# mixer.net
KiCad netlist of a schematic drawn in EAGLE
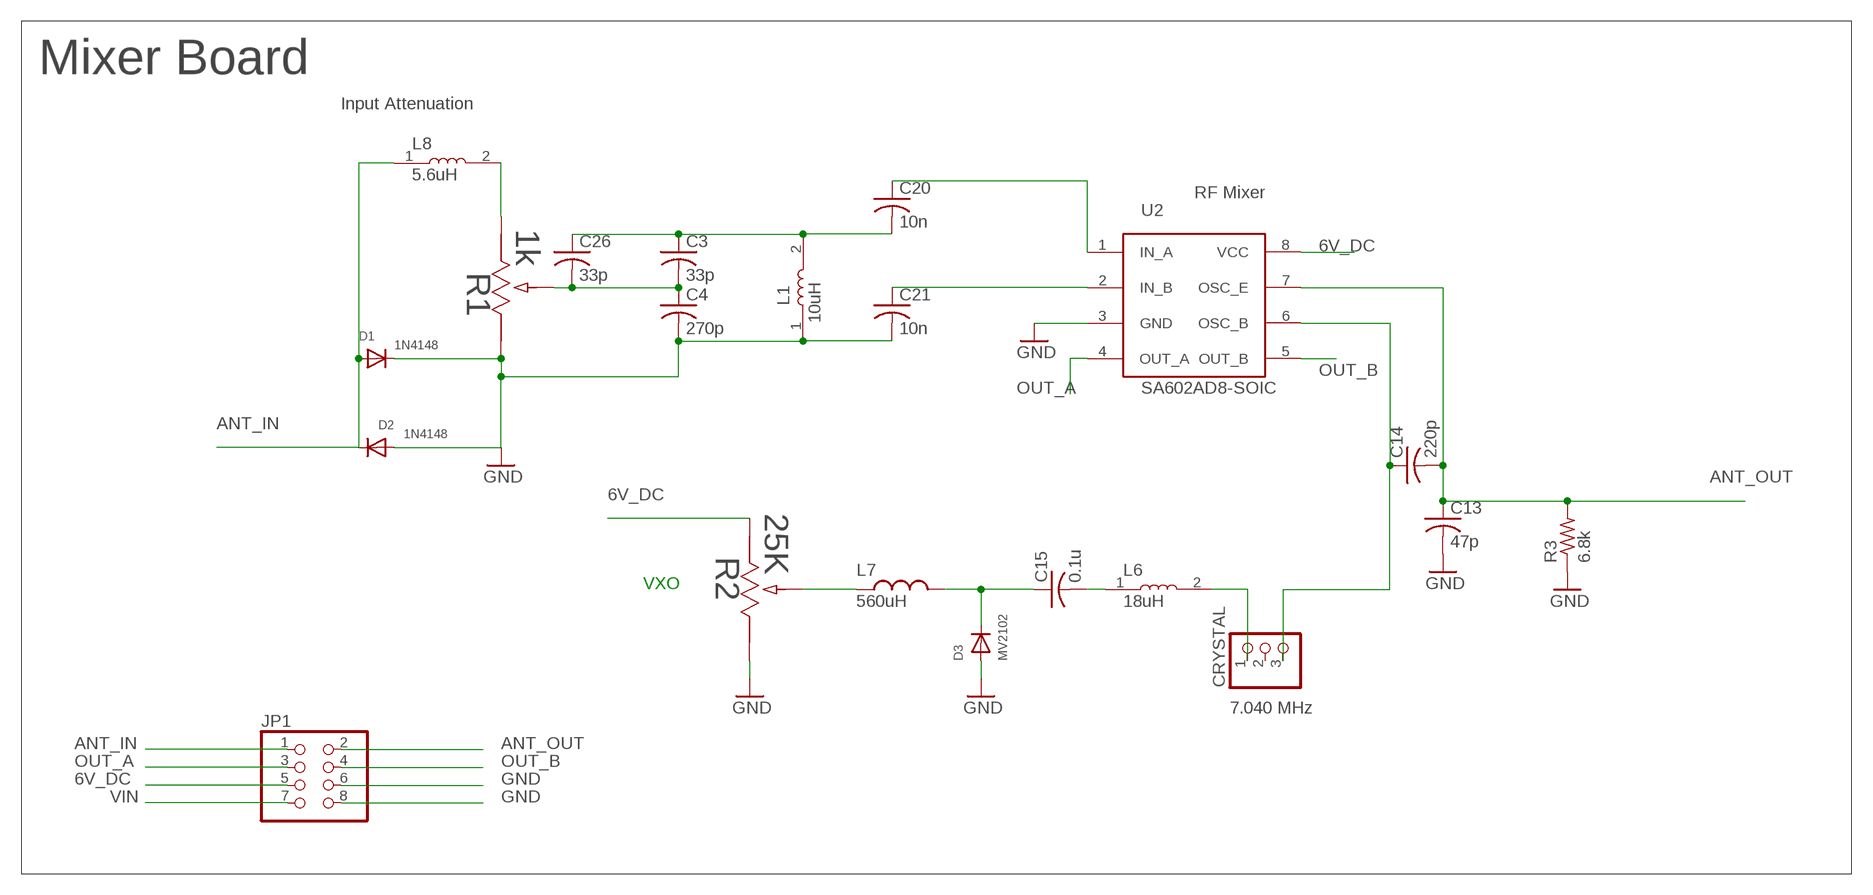
[diagram p0: schematic, sheet 1]

(export (version "E")
  (design (tool "Eeschema 10.0.6"))
  (components
    (comp (ref "C3")
      (value "33p")
      (footprint "eagle-import:C0805")
      (libsource (lib "eagle-import") (part "C-USC0805"))
    )
    (comp (ref "C4")
      (value "270p")
      (footprint "eagle-import:C0805")
      (libsource (lib "eagle-import") (part "C-USC0805"))
    )
    (comp (ref "C13")
      (value "47p")
      (footprint "eagle-import:C0805")
      (libsource (lib "eagle-import") (part "C-USC0805"))
    )
    (comp (ref "C14")
      (value "220p")
      (footprint "eagle-import:C0805")
      (libsource (lib "eagle-import") (part "C-USC0805"))
    )
    (comp (ref "C15")
      (value "0.1u")
      (footprint "eagle-import:C0805")
      (libsource (lib "eagle-import") (part "C-USC0805"))
    )
    (comp (ref "C20")
      (value "10n")
      (footprint "eagle-import:C0805")
      (libsource (lib "eagle-import") (part "C-USC0805"))
    )
    (comp (ref "C21")
      (value "10n")
      (footprint "eagle-import:C0805")
      (libsource (lib "eagle-import") (part "C-USC0805"))
    )
    (comp (ref "C26")
      (value "33p")
      (footprint "eagle-import:C0805")
      (libsource (lib "eagle-import") (part "C-USC0805"))
    )
    (comp (ref "CRYSTAL")
      (value "PINHD-1X3")
      (footprint "eagle-import:1X03")
      (libsource (lib "eagle-import") (part "PINHD-1X3"))
    )
    (comp (ref "D1")
      (value "1N4148")
      (footprint "eagle-import:SOD-123FL")
      (libsource (lib "eagle-import") (part "DIODE_SOD-123FL"))
    )
    (comp (ref "D2")
      (value "1N4148")
      (footprint "eagle-import:SOD-123FL")
      (libsource (lib "eagle-import") (part "DIODE_SOD-123FL"))
    )
    (comp (ref "D3")
      (value "MV2102")
      (footprint "eagle-import:SOD-323F")
      (libsource (lib "eagle-import") (part "DIODESOD-323F"))
    )
    (comp (ref "JP1")
      (value "PINHD-2X4")
      (footprint "eagle-import:2X04")
      (libsource (lib "eagle-import") (part "PINHD-2X4"))
    )
    (comp (ref "L1")
      (value "10uH")
      (footprint "eagle-import:INDC2012X87N")
      (fields (field (name "MF") "TDK") (field (name "MP") "MLF2012E5R6KT000"))
      (libsource (lib "eagle-import") (part "MLF2012E5R6KT000"))
    )
    (comp (ref "L6")
      (value "18uH")
      (footprint "eagle-import:INDC2012X87N")
      (fields (field (name "MF") "TDK") (field (name "MP") "MLF2012E5R6KT000"))
      (libsource (lib "eagle-import") (part "MLF2012E5R6KT000"))
    )
    (comp (ref "L7")
      (value "560uH")
      (footprint "eagle-import:INDM4532X340")
      (libsource (lib "eagle-import") (part "zort2_LMOLDED-1812(4532-METRIC)"))
    )
    (comp (ref "L8")
      (value "5.6uH")
      (footprint "eagle-import:INDC2012X87N")
      (fields (field (name "MF") "TDK") (field (name "MP") "MLF2012E5R6KT000"))
      (libsource (lib "eagle-import") (part "MLF2012E5R6KT000"))
    )
    (comp (ref "R1")
      (value "1k")
      (footprint "eagle-import:POT_3362W")
      (fields (field (name "MANUFACTURER_PART_NUMBER") "3362W-1-102LF"))
      (libsource (lib "eagle-import") (part "3362W-1-102LF"))
    )
    (comp (ref "R2")
      (value "25K")
      (footprint "eagle-import:POT_3362W")
      (fields (field (name "MANUFACTURER_PART_NUMBER") "3362W-1-102LF"))
      (libsource (lib "eagle-import") (part "3362W-1-102LF"))
    )
    (comp (ref "R3")
      (value "6.8k")
      (footprint "eagle-import:M0805")
      (libsource (lib "eagle-import") (part "R-US_M0805"))
    )
    (comp (ref "U2")
      (value "SA602AD8-SOIC")
      (footprint "eagle-import:SOIC127P599X175-8N")
      (libsource (lib "eagle-import") (part "SA602AD8-SOIC"))
    )
  )
  (nets
    (net (code "1") (name "/6V_DC") (class "Default")
      (node (ref "JP1") (pin "5") (pinfunction "5_5") (pintype "passive"))
      (node (ref "R2") (pin "1") (pinfunction "1_1") (pintype "passive"))
      (node (ref "U2") (pin "8") (pinfunction "VCC_8") (pintype "bidirectional"))
    )
    (net (code "2") (name "/ANT_IN") (class "Default")
      (node (ref "D1") (pin "A") (pinfunction "A_A") (pintype "passive"))
      (node (ref "D2") (pin "C") (pinfunction "C_C") (pintype "passive"))
      (node (ref "JP1") (pin "1") (pinfunction "1_1") (pintype "passive"))
      (node (ref "L8") (pin "1") (pinfunction "1_1") (pintype "passive"))
    )
    (net (code "3") (name "/ANT_OUT") (class "Default")
      (node (ref "C13") (pin "1") (pinfunction "1_1") (pintype "passive"))
      (node (ref "C14") (pin "2") (pinfunction "2_2") (pintype "passive"))
      (node (ref "JP1") (pin "2") (pinfunction "2_2") (pintype "passive"))
      (node (ref "R3") (pin "2") (pinfunction "2_2") (pintype "passive"))
      (node (ref "U2") (pin "7") (pinfunction "OSC_E_7") (pintype "bidirectional"))
    )
    (net (code "4") (name "/OUT_A") (class "Default")
      (node (ref "JP1") (pin "3") (pinfunction "3_3") (pintype "passive"))
      (node (ref "U2") (pin "4") (pinfunction "OUT_A_4") (pintype "bidirectional"))
    )
    (net (code "5") (name "/OUT_B") (class "Default")
      (node (ref "JP1") (pin "4") (pinfunction "4_4") (pintype "passive"))
      (node (ref "U2") (pin "5") (pinfunction "OUT_B_5") (pintype "bidirectional"))
    )
    (net (code "6") (name "/VIN") (class "Default")
      (node (ref "JP1") (pin "7") (pinfunction "7_7") (pintype "passive"))
    )
    (net (code "7") (name "GND") (class "Default")
      (node (ref "C13") (pin "2") (pinfunction "2_2") (pintype "passive"))
      (node (ref "C21") (pin "2") (pinfunction "2_2") (pintype "passive"))
      (node (ref "C4") (pin "2") (pinfunction "2_2") (pintype "passive"))
      (node (ref "D1") (pin "C") (pinfunction "C_C") (pintype "passive"))
      (node (ref "D2") (pin "A") (pinfunction "A_A") (pintype "passive"))
      (node (ref "D3") (pin "A") (pinfunction "A_A") (pintype "passive"))
      (node (ref "JP1") (pin "6") (pinfunction "6_6") (pintype "passive"))
      (node (ref "JP1") (pin "8") (pinfunction "8_8") (pintype "passive"))
      (node (ref "L1") (pin "1") (pinfunction "1_1") (pintype "passive"))
      (node (ref "R1") (pin "3") (pinfunction "3_3") (pintype "passive"))
      (node (ref "R2") (pin "3") (pinfunction "3_3") (pintype "passive"))
      (node (ref "R3") (pin "1") (pinfunction "1_1") (pintype "passive"))
      (node (ref "U2") (pin "3") (pinfunction "GND_3") (pintype "bidirectional"))
    )
    (net (code "8") (name "Net-(C15-Pad1)") (class "Default")
      (node (ref "C15") (pin "1") (pinfunction "1_1") (pintype "passive"))
      (node (ref "D3") (pin "C") (pinfunction "C_C") (pintype "passive"))
      (node (ref "L7") (pin "2") (pinfunction "2_2") (pintype "passive"))
    )
    (net (code "9") (name "Net-(C15-Pad2)") (class "Default")
      (node (ref "C15") (pin "2") (pinfunction "2_2") (pintype "passive"))
      (node (ref "L6") (pin "1") (pinfunction "1_1") (pintype "passive"))
    )
    (net (code "10") (name "Net-(C20-Pad2)") (class "Default")
      (node (ref "C20") (pin "2") (pinfunction "2_2") (pintype "passive"))
      (node (ref "C26") (pin "1") (pinfunction "1_1") (pintype "passive"))
      (node (ref "C3") (pin "1") (pinfunction "1_1") (pintype "passive"))
      (node (ref "L1") (pin "2") (pinfunction "2_2") (pintype "passive"))
    )
    (net (code "11") (name "Net-(C26-Pad2)") (class "Default")
      (node (ref "C26") (pin "2") (pinfunction "2_2") (pintype "passive"))
      (node (ref "C3") (pin "2") (pinfunction "2_2") (pintype "passive"))
      (node (ref "C4") (pin "1") (pinfunction "1_1") (pintype "passive"))
      (node (ref "R1") (pin "2") (pinfunction "2_2") (pintype "passive"))
    )
    (net (code "12") (name "Net-(CRYSTAL-Pad1)") (class "Default")
      (node (ref "CRYSTAL") (pin "1") (pinfunction "1_1") (pintype "passive"))
      (node (ref "L6") (pin "2") (pinfunction "2_2") (pintype "passive"))
    )
    (net (code "13") (name "Net-(L7-Pad1)") (class "Default")
      (node (ref "L7") (pin "1") (pinfunction "1_1") (pintype "passive"))
      (node (ref "R2") (pin "2") (pinfunction "2_2") (pintype "passive"))
    )
    (net (code "14") (name "Net-(L8-Pad2)") (class "Default")
      (node (ref "L8") (pin "2") (pinfunction "2_2") (pintype "passive"))
      (node (ref "R1") (pin "1") (pinfunction "1_1") (pintype "passive"))
    )
    (net (code "15") (name "Net-(U2-IN_A)") (class "Default")
      (node (ref "C20") (pin "1") (pinfunction "1_1") (pintype "passive"))
      (node (ref "U2") (pin "1") (pinfunction "IN_A_1") (pintype "bidirectional"))
    )
    (net (code "16") (name "Net-(U2-IN_B)") (class "Default")
      (node (ref "C21") (pin "1") (pinfunction "1_1") (pintype "passive"))
      (node (ref "U2") (pin "2") (pinfunction "IN_B_2") (pintype "bidirectional"))
    )
    (net (code "17") (name "Net-(U2-OSC_B)") (class "Default")
      (node (ref "C14") (pin "1") (pinfunction "1_1") (pintype "passive"))
      (node (ref "CRYSTAL") (pin "3") (pinfunction "3_3") (pintype "passive"))
      (node (ref "U2") (pin "6") (pinfunction "OSC_B_6") (pintype "bidirectional"))
    )
    (net (code "18") (name "unconnected-(CRYSTAL-Pad2)") (class "Default")
      (node (ref "CRYSTAL") (pin "2") (pinfunction "2_2") (pintype "passive"))
    )
  )
)
